# table4_vd4.net
KiCad netlist of a schematic drawn in EasyEDA
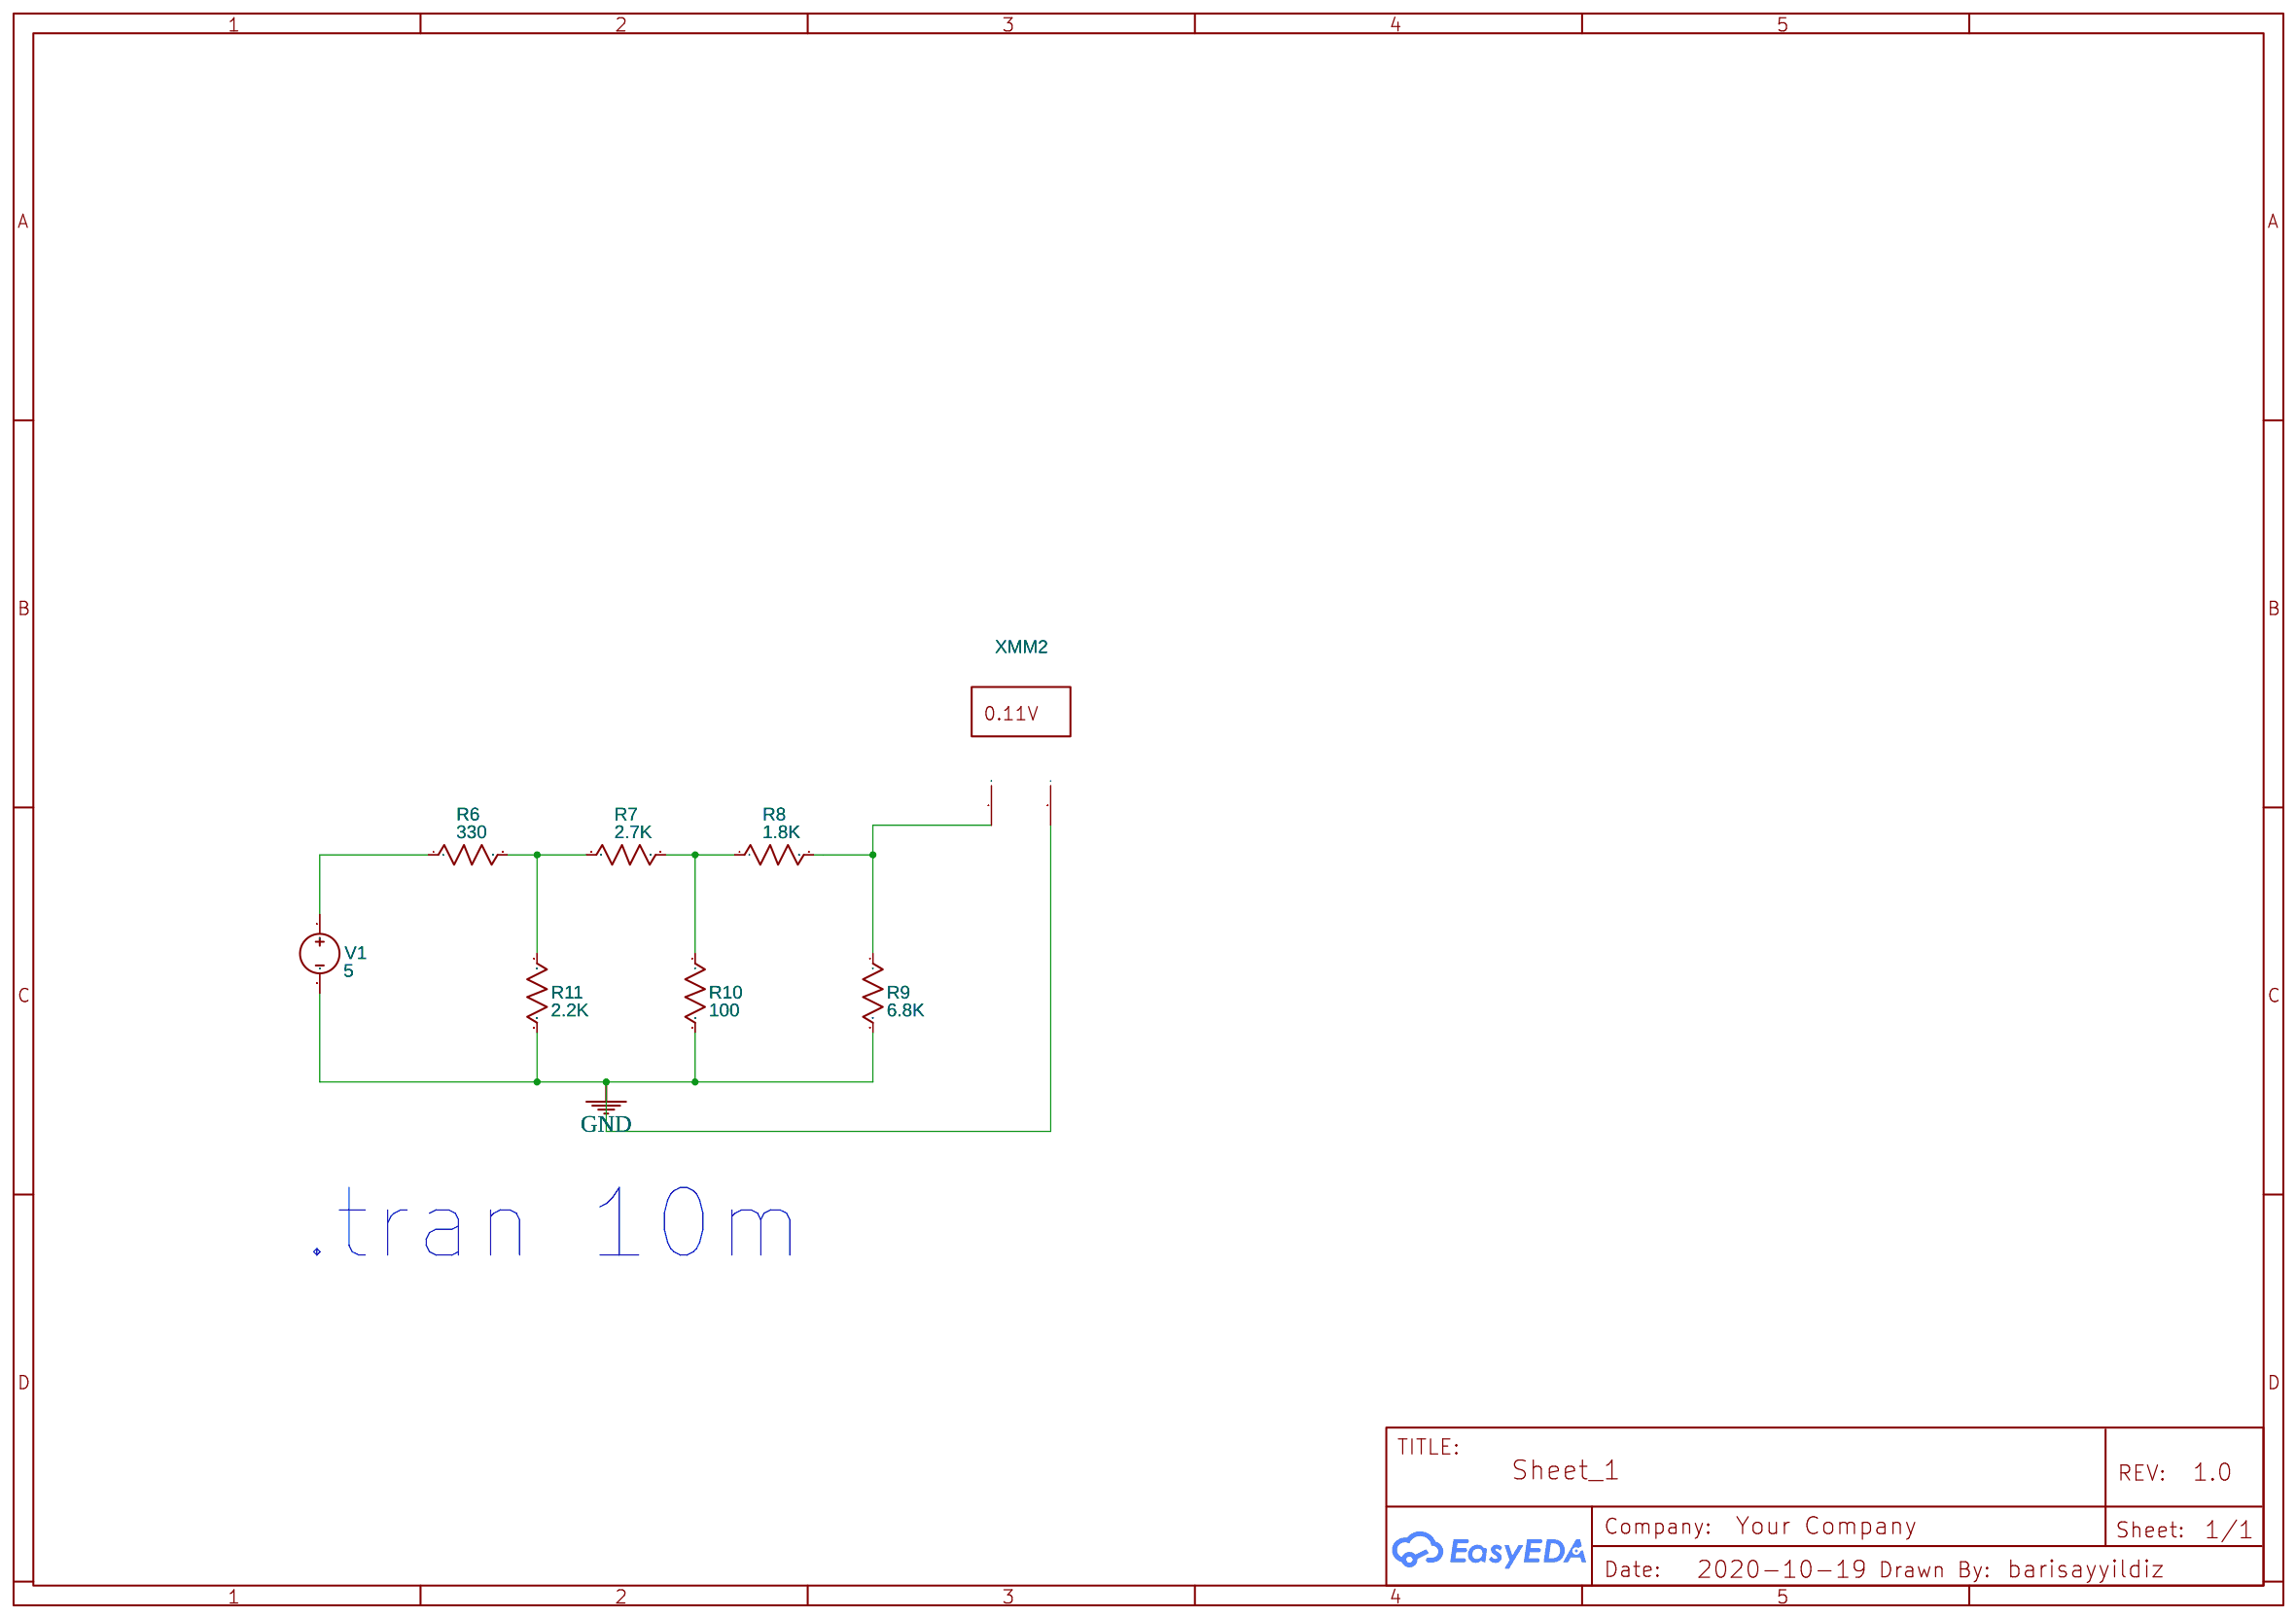
[diagram p0: schematic sheet]

(export (version "E")
  (design (tool "Eeschema 10.0.6"))
  (components
    (comp (ref "R6") (value "330") (libsource (lib "") (part "Resistor_US")))
    (comp (ref "R7") (value "2.7K") (libsource (lib "") (part "Resistor_US")))
    (comp (ref "R8") (value "1.8K") (libsource (lib "") (part "Resistor_US")))
    (comp (ref "R9") (value "6.8K") (libsource (lib "") (part "Resistor_US_1")))
    (comp (ref "R10") (value "100") (libsource (lib "") (part "Resistor_US_1")))
    (comp (ref "R11") (value "2.2K") (libsource (lib "") (part "Resistor_US_1")))
    (comp (ref "V1") (value "5") (libsource (lib "") (part "VDC")))
    (comp (ref "XMM2") (value "Multimeter") (libsource (lib "") (part "MULTIMETER")))
  )
  (nets
    (net (code "1") (name "GND") (class "Default")
      (node (ref "R10") (pin "2") (pinfunction "2_2") (pintype "unspecified"))
      (node (ref "R11") (pin "2") (pinfunction "2_2") (pintype "unspecified"))
      (node (ref "R9") (pin "2") (pinfunction "2_2") (pintype "unspecified"))
      (node (ref "V1") (pin "2") (pinfunction "2_2") (pintype "unspecified"))
      (node (ref "XMM2") (pin "2") (pinfunction "I_2") (pintype "unspecified"))
    )
    (net (code "2") (name "Net-(R6-Pad1)") (class "Default")
      (node (ref "R6") (pin "1") (pinfunction "1_1") (pintype "unspecified"))
      (node (ref "V1") (pin "1") (pinfunction "1_1") (pintype "unspecified"))
    )
    (net (code "3") (name "Net-(R10-Pad1)") (class "Default")
      (node (ref "R10") (pin "1") (pinfunction "1_1") (pintype "unspecified"))
      (node (ref "R7") (pin "2") (pinfunction "2_2") (pintype "unspecified"))
      (node (ref "R8") (pin "1") (pinfunction "1_1") (pintype "unspecified"))
    )
    (net (code "4") (name "Net-(R11-Pad1)") (class "Default")
      (node (ref "R11") (pin "1") (pinfunction "1_1") (pintype "unspecified"))
      (node (ref "R6") (pin "2") (pinfunction "2_2") (pintype "unspecified"))
      (node (ref "R7") (pin "1") (pinfunction "1_1") (pintype "unspecified"))
    )
    (net (code "5") (name "Net-(XMM2-+)") (class "Default")
      (node (ref "R8") (pin "2") (pinfunction "2_2") (pintype "unspecified"))
      (node (ref "R9") (pin "1") (pinfunction "1_1") (pintype "unspecified"))
      (node (ref "XMM2") (pin "1") (pinfunction "+_1") (pintype "unspecified"))
    )
  )
)
